# WattMeter-PowerSocket-Controller_V1_00.net
KiCad netlist of a schematic drawn in EAGLE
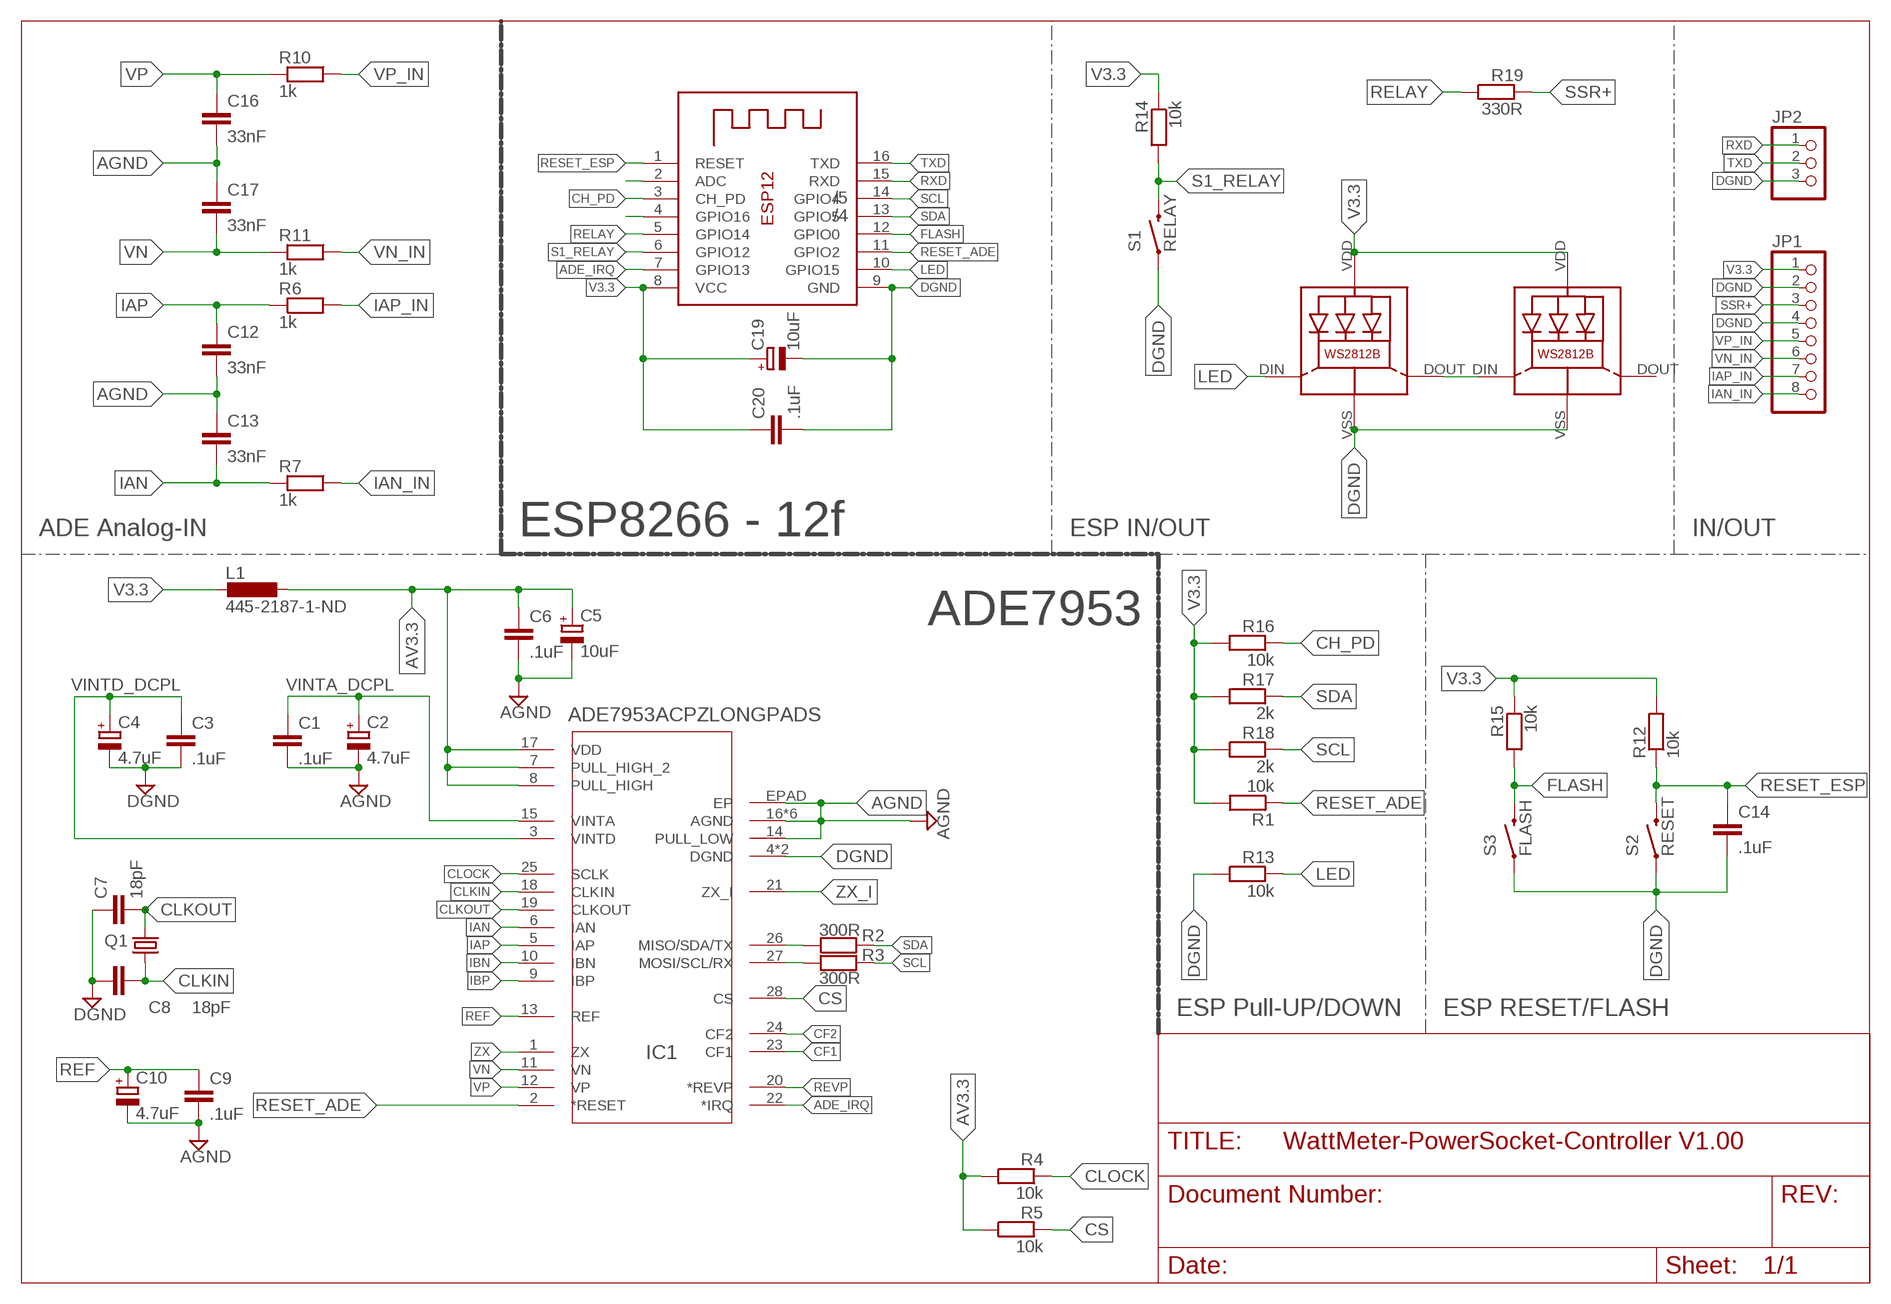
[diagram p0: schematic, sheet 1]

(export (version "E")
  (design (tool "Eeschema 10.0.6"))
  (components
    (comp (ref "C1")
      (value ".1uF")
      (footprint "eagle-import:C0805K@1")
      (libsource (lib "eagle-import") (part "C-EUC0805K"))
    )
    (comp (ref "C2")
      (value "4.7uF")
      (footprint "eagle-import:A_3216-18R")
      (libsource (lib "eagle-import") (part "CPOL-EUA/3216-18R"))
    )
    (comp (ref "C3")
      (value ".1uF")
      (footprint "eagle-import:C0805K@1")
      (libsource (lib "eagle-import") (part "C-EUC0805K"))
    )
    (comp (ref "C4")
      (value "4.7uF")
      (footprint "eagle-import:A_3216-18R")
      (libsource (lib "eagle-import") (part "CPOL-EUA/3216-18R"))
    )
    (comp (ref "C5")
      (value "10uF")
      (footprint "eagle-import:A_3216-18R")
      (libsource (lib "eagle-import") (part "CPOL-EUA/3216-18R"))
    )
    (comp (ref "C6")
      (value ".1uF")
      (footprint "eagle-import:C0805K@1")
      (libsource (lib "eagle-import") (part "C-EUC0805K"))
    )
    (comp (ref "C7")
      (value "18pF")
      (footprint "eagle-import:C0805K@1")
      (libsource (lib "eagle-import") (part "C-EUC0805K"))
    )
    (comp (ref "C8")
      (value "18pF")
      (footprint "eagle-import:C0805K@1")
      (libsource (lib "eagle-import") (part "C-EUC0805K"))
    )
    (comp (ref "C9")
      (value ".1uF")
      (footprint "eagle-import:C0805K@1")
      (libsource (lib "eagle-import") (part "C-EUC0805K"))
    )
    (comp (ref "C10")
      (value "4.7uF")
      (footprint "eagle-import:A_3216-18R")
      (libsource (lib "eagle-import") (part "CPOL-EUA/3216-18R"))
    )
    (comp (ref "C12")
      (value "33nF")
      (footprint "eagle-import:C0805K@1")
      (libsource (lib "eagle-import") (part "C-EUC0805K"))
    )
    (comp (ref "C13")
      (value "33nF")
      (footprint "eagle-import:C0805K@1")
      (libsource (lib "eagle-import") (part "C-EUC0805K"))
    )
    (comp (ref "C14")
      (value ".1uF")
      (footprint "eagle-import:C0805K@1")
      (libsource (lib "eagle-import") (part "C-EUC0805K"))
    )
    (comp (ref "C16")
      (value "33nF")
      (footprint "eagle-import:C0805K@1")
      (libsource (lib "eagle-import") (part "C-EUC0805K"))
    )
    (comp (ref "C17")
      (value "33nF")
      (footprint "eagle-import:C0805K@1")
      (libsource (lib "eagle-import") (part "C-EUC0805K"))
    )
    (comp (ref "C19")
      (value "10uF")
      (footprint "eagle-import:A_3216-18R")
      (libsource (lib "eagle-import") (part "CPOL-EUA/3216-18R"))
    )
    (comp (ref "C20")
      (value ".1uF")
      (footprint "eagle-import:C0805K@1")
      (libsource (lib "eagle-import") (part "C-EUC0805K"))
    )
    (comp (ref "IC1")
      (value "ADE7953ACPZLONGPADS")
      (footprint "eagle-import:VQFN-28-D")
      (libsource (lib "eagle-import") (part "ADE7953ACPZ5.0"))
    )
    (comp (ref "JP1")
      (value "PINHD-1X8")
      (footprint "eagle-import:1X08")
      (libsource (lib "eagle-import") (part "PINHD-1X8"))
    )
    (comp (ref "JP2")
      (value "PINHD-1X3")
      (footprint "eagle-import:1X03")
      (libsource (lib "eagle-import") (part "PINHD-1X3"))
    )
    (comp (ref "L1")
      (value "445-2187-1-ND")
      (footprint "eagle-import:L2012C")
      (libsource (lib "eagle-import") (part "L-EUL2012C"))
    )
    (comp (ref "LED1")
      (value "WS2812B")
      (footprint "eagle-import:WS2812B")
      (libsource (lib "eagle-import") (part "WS2812B"))
    )
    (comp (ref "LED2")
      (value "WS2812B")
      (footprint "eagle-import:WS2812B")
      (libsource (lib "eagle-import") (part "WS2812B"))
    )
    (comp (ref "Q1")
      (value "535-10200-1-ND")
      (footprint "eagle-import:SM49")
      (libsource (lib "eagle-import") (part "CRYSTALSM49"))
    )
    (comp (ref "R1")
      (value "10k")
      (footprint "eagle-import:R0805@1")
      (libsource (lib "eagle-import") (part "R-US_R0805"))
    )
    (comp (ref "R2")
      (value "300R")
      (footprint "eagle-import:R0805@1")
      (libsource (lib "eagle-import") (part "R-US_R0805"))
    )
    (comp (ref "R3")
      (value "300R")
      (footprint "eagle-import:R0805@1")
      (libsource (lib "eagle-import") (part "R-US_R0805"))
    )
    (comp (ref "R4")
      (value "10k")
      (footprint "eagle-import:R0805@1")
      (libsource (lib "eagle-import") (part "R-US_R0805"))
    )
    (comp (ref "R5")
      (value "10k")
      (footprint "eagle-import:R0805@1")
      (libsource (lib "eagle-import") (part "R-US_R0805"))
    )
    (comp (ref "R6")
      (value "1k")
      (footprint "eagle-import:R0805@1")
      (libsource (lib "eagle-import") (part "R-US_R0805"))
    )
    (comp (ref "R7")
      (value "1k")
      (footprint "eagle-import:R0805@1")
      (libsource (lib "eagle-import") (part "R-US_R0805"))
    )
    (comp (ref "R10")
      (value "1k")
      (footprint "eagle-import:R0805@1")
      (libsource (lib "eagle-import") (part "R-US_R0805"))
    )
    (comp (ref "R11")
      (value "1k")
      (footprint "eagle-import:R0805@1")
      (libsource (lib "eagle-import") (part "R-US_R0805"))
    )
    (comp (ref "R12")
      (value "10k")
      (footprint "eagle-import:R0805@1")
      (libsource (lib "eagle-import") (part "R-US_R0805"))
    )
    (comp (ref "R13")
      (value "10k")
      (footprint "eagle-import:R0805@1")
      (libsource (lib "eagle-import") (part "R-US_R0805"))
    )
    (comp (ref "R14")
      (value "10k")
      (footprint "eagle-import:R0805@1")
      (libsource (lib "eagle-import") (part "R-US_R0805"))
    )
    (comp (ref "R15")
      (value "10k")
      (footprint "eagle-import:R0805@1")
      (libsource (lib "eagle-import") (part "R-US_R0805"))
    )
    (comp (ref "R16")
      (value "10k")
      (footprint "eagle-import:R0805@1")
      (libsource (lib "eagle-import") (part "R-US_R0805"))
    )
    (comp (ref "R17")
      (value "2k")
      (footprint "eagle-import:R0805@1")
      (libsource (lib "eagle-import") (part "R-US_R0805"))
    )
    (comp (ref "R18")
      (value "2k")
      (footprint "eagle-import:R0805@1")
      (libsource (lib "eagle-import") (part "R-US_R0805"))
    )
    (comp (ref "R19")
      (value "330R")
      (footprint "eagle-import:R0805@1")
      (libsource (lib "eagle-import") (part "R-US_R0805"))
    )
    (comp (ref "S1")
      (value "RELAY")
      (footprint "eagle-import:TACTILE-SWITCH-SMD")
      (libsource (lib "eagle-import") (part "SWITCH-MOMENTARY-2SMD"))
    )
    (comp (ref "S2")
      (value "RESET")
      (footprint "eagle-import:TACTILE-SWITCH-1101NE")
      (libsource (lib "eagle-import") (part "SWITCH-MOMENTARY-2SMD-1101NE"))
    )
    (comp (ref "S3")
      (value "FLASH")
      (footprint "eagle-import:TACTILE-SWITCH-1101NE")
      (libsource (lib "eagle-import") (part "SWITCH-MOMENTARY-2SMD-1101NE"))
    )
    (comp (ref "X1")
      (value "ESP-12")
      (footprint "eagle-import:ESP-12")
      (libsource (lib "eagle-import") (part "ESP-12"))
    )
  )
  (nets
    (net (code "1") (name "/VINTA_DCPL") (class "Default")
      (node (ref "C1") (pin "1") (pinfunction "1_1") (pintype "passive"))
      (node (ref "C2") (pin "+") (pinfunction "+_+") (pintype "passive"))
      (node (ref "IC1") (pin "15") (pinfunction "VINTA_15") (pintype "passive"))
    )
    (net (code "2") (name "/VINTD_DCPL") (class "Default")
      (node (ref "C3") (pin "1") (pinfunction "1_1") (pintype "passive"))
      (node (ref "C4") (pin "+") (pinfunction "+_+") (pintype "passive"))
      (node (ref "IC1") (pin "3") (pinfunction "VINTD_3") (pintype "passive"))
    )
    (net (code "3") (name "ADE_IRQ") (class "Default")
      (node (ref "IC1") (pin "22") (pinfunction "*IRQ_22") (pintype "passive"))
      (node (ref "X1") (pin "7") (pinfunction "GPIO13_7") (pintype "bidirectional"))
    )
    (net (code "4") (name "AGND") (class "Default")
      (node (ref "C1") (pin "2") (pinfunction "2_2") (pintype "passive"))
      (node (ref "C10") (pin "-") (pinfunction "-_-") (pintype "passive"))
      (node (ref "C12") (pin "2") (pinfunction "2_2") (pintype "passive"))
      (node (ref "C13") (pin "1") (pinfunction "1_1") (pintype "passive"))
      (node (ref "C16") (pin "2") (pinfunction "2_2") (pintype "passive"))
      (node (ref "C17") (pin "1") (pinfunction "1_1") (pintype "passive"))
      (node (ref "C2") (pin "-") (pinfunction "-_-") (pintype "passive"))
      (node (ref "C5") (pin "-") (pinfunction "-_-") (pintype "passive"))
      (node (ref "C6") (pin "2") (pinfunction "2_2") (pintype "passive"))
      (node (ref "C9") (pin "2") (pinfunction "2_2") (pintype "passive"))
      (node (ref "IC1") (pin "14") (pinfunction "PULL_LOW_14") (pintype "passive"))
      (node (ref "IC1") (pin "16") (pinfunction "AGND_16") (pintype "passive"))
      (node (ref "IC1") (pin "29") (pinfunction "AGND_29") (pintype "passive"))
      (node (ref "IC1") (pin "30") (pinfunction "AGND_30") (pintype "passive"))
      (node (ref "IC1") (pin "31") (pinfunction "AGND_31") (pintype "passive"))
      (node (ref "IC1") (pin "32") (pinfunction "AGND_32") (pintype "passive"))
      (node (ref "IC1") (pin "EPAD") (pinfunction "EP_EPAD") (pintype "passive"))
      (node (ref "IC1") (pin "_AGND") (pinfunction "AGND__AGND") (pintype "passive"))
    )
    (net (code "5") (name "AV3.3") (class "Default")
      (node (ref "C5") (pin "+") (pinfunction "+_+") (pintype "passive"))
      (node (ref "C6") (pin "1") (pinfunction "1_1") (pintype "passive"))
      (node (ref "IC1") (pin "17") (pinfunction "VDD_17") (pintype "passive"))
      (node (ref "IC1") (pin "7") (pinfunction "PULL_HIGH_2_7") (pintype "passive"))
      (node (ref "IC1") (pin "8") (pinfunction "PULL_HIGH_8") (pintype "passive"))
      (node (ref "L1") (pin "1") (pinfunction "1_1") (pintype "passive"))
      (node (ref "R4") (pin "2") (pinfunction "2_2") (pintype "passive"))
      (node (ref "R5") (pin "2") (pinfunction "2_2") (pintype "passive"))
    )
    (net (code "6") (name "CF1") (class "Default")
      (node (ref "IC1") (pin "23") (pinfunction "CF1_23") (pintype "passive"))
    )
    (net (code "7") (name "CF2") (class "Default")
      (node (ref "IC1") (pin "24") (pinfunction "CF2_24") (pintype "passive"))
    )
    (net (code "8") (name "CH_PD") (class "Default")
      (node (ref "R16") (pin "1") (pinfunction "1_1") (pintype "passive"))
      (node (ref "X1") (pin "3") (pinfunction "CH_PD_3") (pintype "input"))
    )
    (net (code "9") (name "CLKIN") (class "Default")
      (node (ref "C8") (pin "2") (pinfunction "2_2") (pintype "passive"))
      (node (ref "IC1") (pin "18") (pinfunction "CLKIN_18") (pintype "passive"))
      (node (ref "Q1") (pin "1") (pinfunction "1_1") (pintype "passive"))
    )
    (net (code "10") (name "CLKOUT") (class "Default")
      (node (ref "C7") (pin "2") (pinfunction "2_2") (pintype "passive"))
      (node (ref "IC1") (pin "19") (pinfunction "CLKOUT_19") (pintype "passive"))
      (node (ref "Q1") (pin "2") (pinfunction "2_2") (pintype "passive"))
    )
    (net (code "11") (name "CLOCK") (class "Default")
      (node (ref "IC1") (pin "25") (pinfunction "SCLK_25") (pintype "passive"))
      (node (ref "R4") (pin "1") (pinfunction "1_1") (pintype "passive"))
    )
    (net (code "12") (name "CS") (class "Default")
      (node (ref "IC1") (pin "28") (pinfunction "CS_28") (pintype "passive"))
      (node (ref "R5") (pin "1") (pinfunction "1_1") (pintype "passive"))
    )
    (net (code "13") (name "DGND") (class "Default")
      (node (ref "C14") (pin "2") (pinfunction "2_2") (pintype "passive"))
      (node (ref "C19") (pin "-") (pinfunction "-_-") (pintype "passive"))
      (node (ref "C20") (pin "2") (pinfunction "2_2") (pintype "passive"))
      (node (ref "C3") (pin "2") (pinfunction "2_2") (pintype "passive"))
      (node (ref "C4") (pin "-") (pinfunction "-_-") (pintype "passive"))
      (node (ref "C7") (pin "1") (pinfunction "1_1") (pintype "passive"))
      (node (ref "C8") (pin "1") (pinfunction "1_1") (pintype "passive"))
      (node (ref "IC1") (pin "4") (pinfunction "DGND_4") (pintype "passive"))
      (node (ref "IC1") (pin "_DGND") (pinfunction "DGND__DGND") (pintype "passive"))
      (node (ref "JP1") (pin "2") (pinfunction "2_2") (pintype "passive"))
      (node (ref "JP1") (pin "4") (pinfunction "4_4") (pintype "passive"))
      (node (ref "JP2") (pin "3") (pinfunction "3_3") (pintype "passive"))
      (node (ref "LED1") (pin "VSS") (pinfunction "GND_VSS") (pintype "power_in"))
      (node (ref "LED2") (pin "VSS") (pinfunction "GND_VSS") (pintype "power_in"))
      (node (ref "R13") (pin "2") (pinfunction "2_2") (pintype "passive"))
      (node (ref "S1") (pin "1") (pinfunction "1_1") (pintype "passive"))
      (node (ref "S2") (pin "1") (pinfunction "1_1") (pintype "passive"))
      (node (ref "S3") (pin "1") (pinfunction "1_1") (pintype "passive"))
      (node (ref "X1") (pin "9") (pinfunction "GND_9") (pintype "power_in"))
    )
    (net (code "14") (name "FLASH") (class "Default")
      (node (ref "R15") (pin "2") (pinfunction "2_2") (pintype "passive"))
      (node (ref "S3") (pin "2") (pinfunction "2_2") (pintype "passive"))
      (node (ref "X1") (pin "12") (pinfunction "GPIO0_12") (pintype "bidirectional"))
    )
    (net (code "15") (name "IAN") (class "Default")
      (node (ref "C13") (pin "2") (pinfunction "2_2") (pintype "passive"))
      (node (ref "IC1") (pin "6") (pinfunction "IAN_6") (pintype "passive"))
      (node (ref "R7") (pin "1") (pinfunction "1_1") (pintype "passive"))
    )
    (net (code "16") (name "IAN_IN") (class "Default")
      (node (ref "JP1") (pin "8") (pinfunction "8_8") (pintype "passive"))
      (node (ref "R7") (pin "2") (pinfunction "2_2") (pintype "passive"))
    )
    (net (code "17") (name "IAP") (class "Default")
      (node (ref "C12") (pin "1") (pinfunction "1_1") (pintype "passive"))
      (node (ref "IC1") (pin "5") (pinfunction "IAP_5") (pintype "passive"))
      (node (ref "R6") (pin "1") (pinfunction "1_1") (pintype "passive"))
    )
    (net (code "18") (name "IAP_IN") (class "Default")
      (node (ref "JP1") (pin "7") (pinfunction "7_7") (pintype "passive"))
      (node (ref "R6") (pin "2") (pinfunction "2_2") (pintype "passive"))
    )
    (net (code "19") (name "IBN") (class "Default")
      (node (ref "IC1") (pin "10") (pinfunction "IBN_10") (pintype "passive"))
    )
    (net (code "20") (name "IBP") (class "Default")
      (node (ref "IC1") (pin "9") (pinfunction "IBP_9") (pintype "passive"))
    )
    (net (code "21") (name "LED") (class "Default")
      (node (ref "LED1") (pin "DIN") (pinfunction "DI_DIN") (pintype "input"))
      (node (ref "R13") (pin "1") (pinfunction "1_1") (pintype "passive"))
      (node (ref "X1") (pin "10") (pinfunction "GPIO15_10") (pintype "bidirectional"))
    )
    (net (code "22") (name "Net-(IC1-MISO{slash}SDA{slash}TX)") (class "Default")
      (node (ref "IC1") (pin "26") (pinfunction "MISO/SDA/TX_26") (pintype "passive"))
      (node (ref "R2") (pin "1") (pinfunction "1_1") (pintype "passive"))
    )
    (net (code "23") (name "Net-(IC1-MOSI{slash}SCL{slash}RX)") (class "Default")
      (node (ref "IC1") (pin "27") (pinfunction "MOSI/SCL/RX_27") (pintype "passive"))
      (node (ref "R3") (pin "1") (pinfunction "1_1") (pintype "passive"))
    )
    (net (code "24") (name "Net-(LED1-DO)") (class "Default")
      (node (ref "LED1") (pin "DOUT") (pinfunction "DO_DOUT") (pintype "output"))
      (node (ref "LED2") (pin "DIN") (pinfunction "DI_DIN") (pintype "input"))
    )
    (net (code "25") (name "REF") (class "Default")
      (node (ref "C10") (pin "+") (pinfunction "+_+") (pintype "passive"))
      (node (ref "C9") (pin "1") (pinfunction "1_1") (pintype "passive"))
      (node (ref "IC1") (pin "13") (pinfunction "REF_13") (pintype "passive"))
    )
    (net (code "26") (name "RELAY") (class "Default")
      (node (ref "R19") (pin "2") (pinfunction "2_2") (pintype "passive"))
      (node (ref "X1") (pin "5") (pinfunction "GPIO14_5") (pintype "bidirectional"))
    )
    (net (code "27") (name "RESET_ADE") (class "Default")
      (node (ref "IC1") (pin "2") (pinfunction "*RESET_2") (pintype "passive"))
      (node (ref "R1") (pin "1") (pinfunction "1_1") (pintype "passive"))
      (node (ref "X1") (pin "11") (pinfunction "GPIO2_11") (pintype "bidirectional"))
    )
    (net (code "28") (name "RESET_ESP") (class "Default")
      (node (ref "C14") (pin "1") (pinfunction "1_1") (pintype "passive"))
      (node (ref "R12") (pin "1") (pinfunction "1_1") (pintype "passive"))
      (node (ref "S2") (pin "2") (pinfunction "2_2") (pintype "passive"))
      (node (ref "X1") (pin "1") (pinfunction "RESET_1") (pintype "input"))
    )
    (net (code "29") (name "REVP") (class "Default")
      (node (ref "IC1") (pin "20") (pinfunction "*REVP_20") (pintype "passive"))
    )
    (net (code "30") (name "RXD") (class "Default")
      (node (ref "JP2") (pin "1") (pinfunction "1_1") (pintype "passive"))
      (node (ref "X1") (pin "15") (pinfunction "RXD_15") (pintype "input"))
    )
    (net (code "31") (name "S1_RELAY") (class "Default")
      (node (ref "R14") (pin "2") (pinfunction "2_2") (pintype "passive"))
      (node (ref "S1") (pin "3") (pinfunction "2_3") (pintype "passive"))
      (node (ref "X1") (pin "6") (pinfunction "GPIO12_6") (pintype "bidirectional"))
    )
    (net (code "32") (name "SCL") (class "Default")
      (node (ref "R18") (pin "1") (pinfunction "1_1") (pintype "passive"))
      (node (ref "R3") (pin "2") (pinfunction "2_2") (pintype "passive"))
      (node (ref "X1") (pin "14") (pinfunction "GPIO4_14") (pintype "bidirectional"))
    )
    (net (code "33") (name "SDA") (class "Default")
      (node (ref "R17") (pin "1") (pinfunction "1_1") (pintype "passive"))
      (node (ref "R2") (pin "2") (pinfunction "2_2") (pintype "passive"))
      (node (ref "X1") (pin "13") (pinfunction "GPIO5_13") (pintype "bidirectional"))
    )
    (net (code "34") (name "SSR+") (class "Default")
      (node (ref "JP1") (pin "3") (pinfunction "3_3") (pintype "passive"))
      (node (ref "R19") (pin "1") (pinfunction "1_1") (pintype "passive"))
    )
    (net (code "35") (name "TXD") (class "Default")
      (node (ref "JP2") (pin "2") (pinfunction "2_2") (pintype "passive"))
      (node (ref "X1") (pin "16") (pinfunction "TXD_16") (pintype "output"))
    )
    (net (code "36") (name "V3.3") (class "Default")
      (node (ref "C19") (pin "+") (pinfunction "+_+") (pintype "passive"))
      (node (ref "C20") (pin "1") (pinfunction "1_1") (pintype "passive"))
      (node (ref "JP1") (pin "1") (pinfunction "1_1") (pintype "passive"))
      (node (ref "L1") (pin "2") (pinfunction "2_2") (pintype "passive"))
      (node (ref "LED1") (pin "VDD") (pinfunction "VDD_VDD") (pintype "power_in"))
      (node (ref "LED2") (pin "VDD") (pinfunction "VDD_VDD") (pintype "power_in"))
      (node (ref "R1") (pin "2") (pinfunction "2_2") (pintype "passive"))
      (node (ref "R12") (pin "2") (pinfunction "2_2") (pintype "passive"))
      (node (ref "R14") (pin "1") (pinfunction "1_1") (pintype "passive"))
      (node (ref "R15") (pin "1") (pinfunction "1_1") (pintype "passive"))
      (node (ref "R16") (pin "2") (pinfunction "2_2") (pintype "passive"))
      (node (ref "R17") (pin "2") (pinfunction "2_2") (pintype "passive"))
      (node (ref "R18") (pin "2") (pinfunction "2_2") (pintype "passive"))
      (node (ref "X1") (pin "8") (pinfunction "VCC_8") (pintype "power_in"))
    )
    (net (code "37") (name "VN") (class "Default")
      (node (ref "C17") (pin "2") (pinfunction "2_2") (pintype "passive"))
      (node (ref "IC1") (pin "11") (pinfunction "VN_11") (pintype "passive"))
      (node (ref "R11") (pin "1") (pinfunction "1_1") (pintype "passive"))
    )
    (net (code "38") (name "VN_IN") (class "Default")
      (node (ref "JP1") (pin "6") (pinfunction "6_6") (pintype "passive"))
      (node (ref "R11") (pin "2") (pinfunction "2_2") (pintype "passive"))
    )
    (net (code "39") (name "VP") (class "Default")
      (node (ref "C16") (pin "1") (pinfunction "1_1") (pintype "passive"))
      (node (ref "IC1") (pin "12") (pinfunction "VP_12") (pintype "passive"))
      (node (ref "R10") (pin "1") (pinfunction "1_1") (pintype "passive"))
    )
    (net (code "40") (name "VP_IN") (class "Default")
      (node (ref "JP1") (pin "5") (pinfunction "5_5") (pintype "passive"))
      (node (ref "R10") (pin "2") (pinfunction "2_2") (pintype "passive"))
    )
    (net (code "41") (name "ZX") (class "Default")
      (node (ref "IC1") (pin "1") (pinfunction "ZX_1") (pintype "passive"))
    )
    (net (code "42") (name "ZX_I") (class "Default")
      (node (ref "IC1") (pin "21") (pinfunction "ZX_I_21") (pintype "passive"))
    )
    (net (code "43") (name "unconnected-(LED2-DO-PadDOUT)") (class "Default")
      (node (ref "LED2") (pin "DOUT") (pinfunction "DO_DOUT") (pintype "output"))
    )
    (net (code "44") (name "unconnected-(X1-ADC-Pad2)") (class "Default")
      (node (ref "X1") (pin "2") (pinfunction "ADC_2") (pintype "passive"))
    )
    (net (code "45") (name "unconnected-(X1-GPIO16-Pad4)") (class "Default")
      (node (ref "X1") (pin "4") (pinfunction "GPIO16_4") (pintype "bidirectional"))
    )
  )
)
